# PGTN021_octasource_mkii_controls.net
KiCad netlist of a schematic drawn in EAGLE
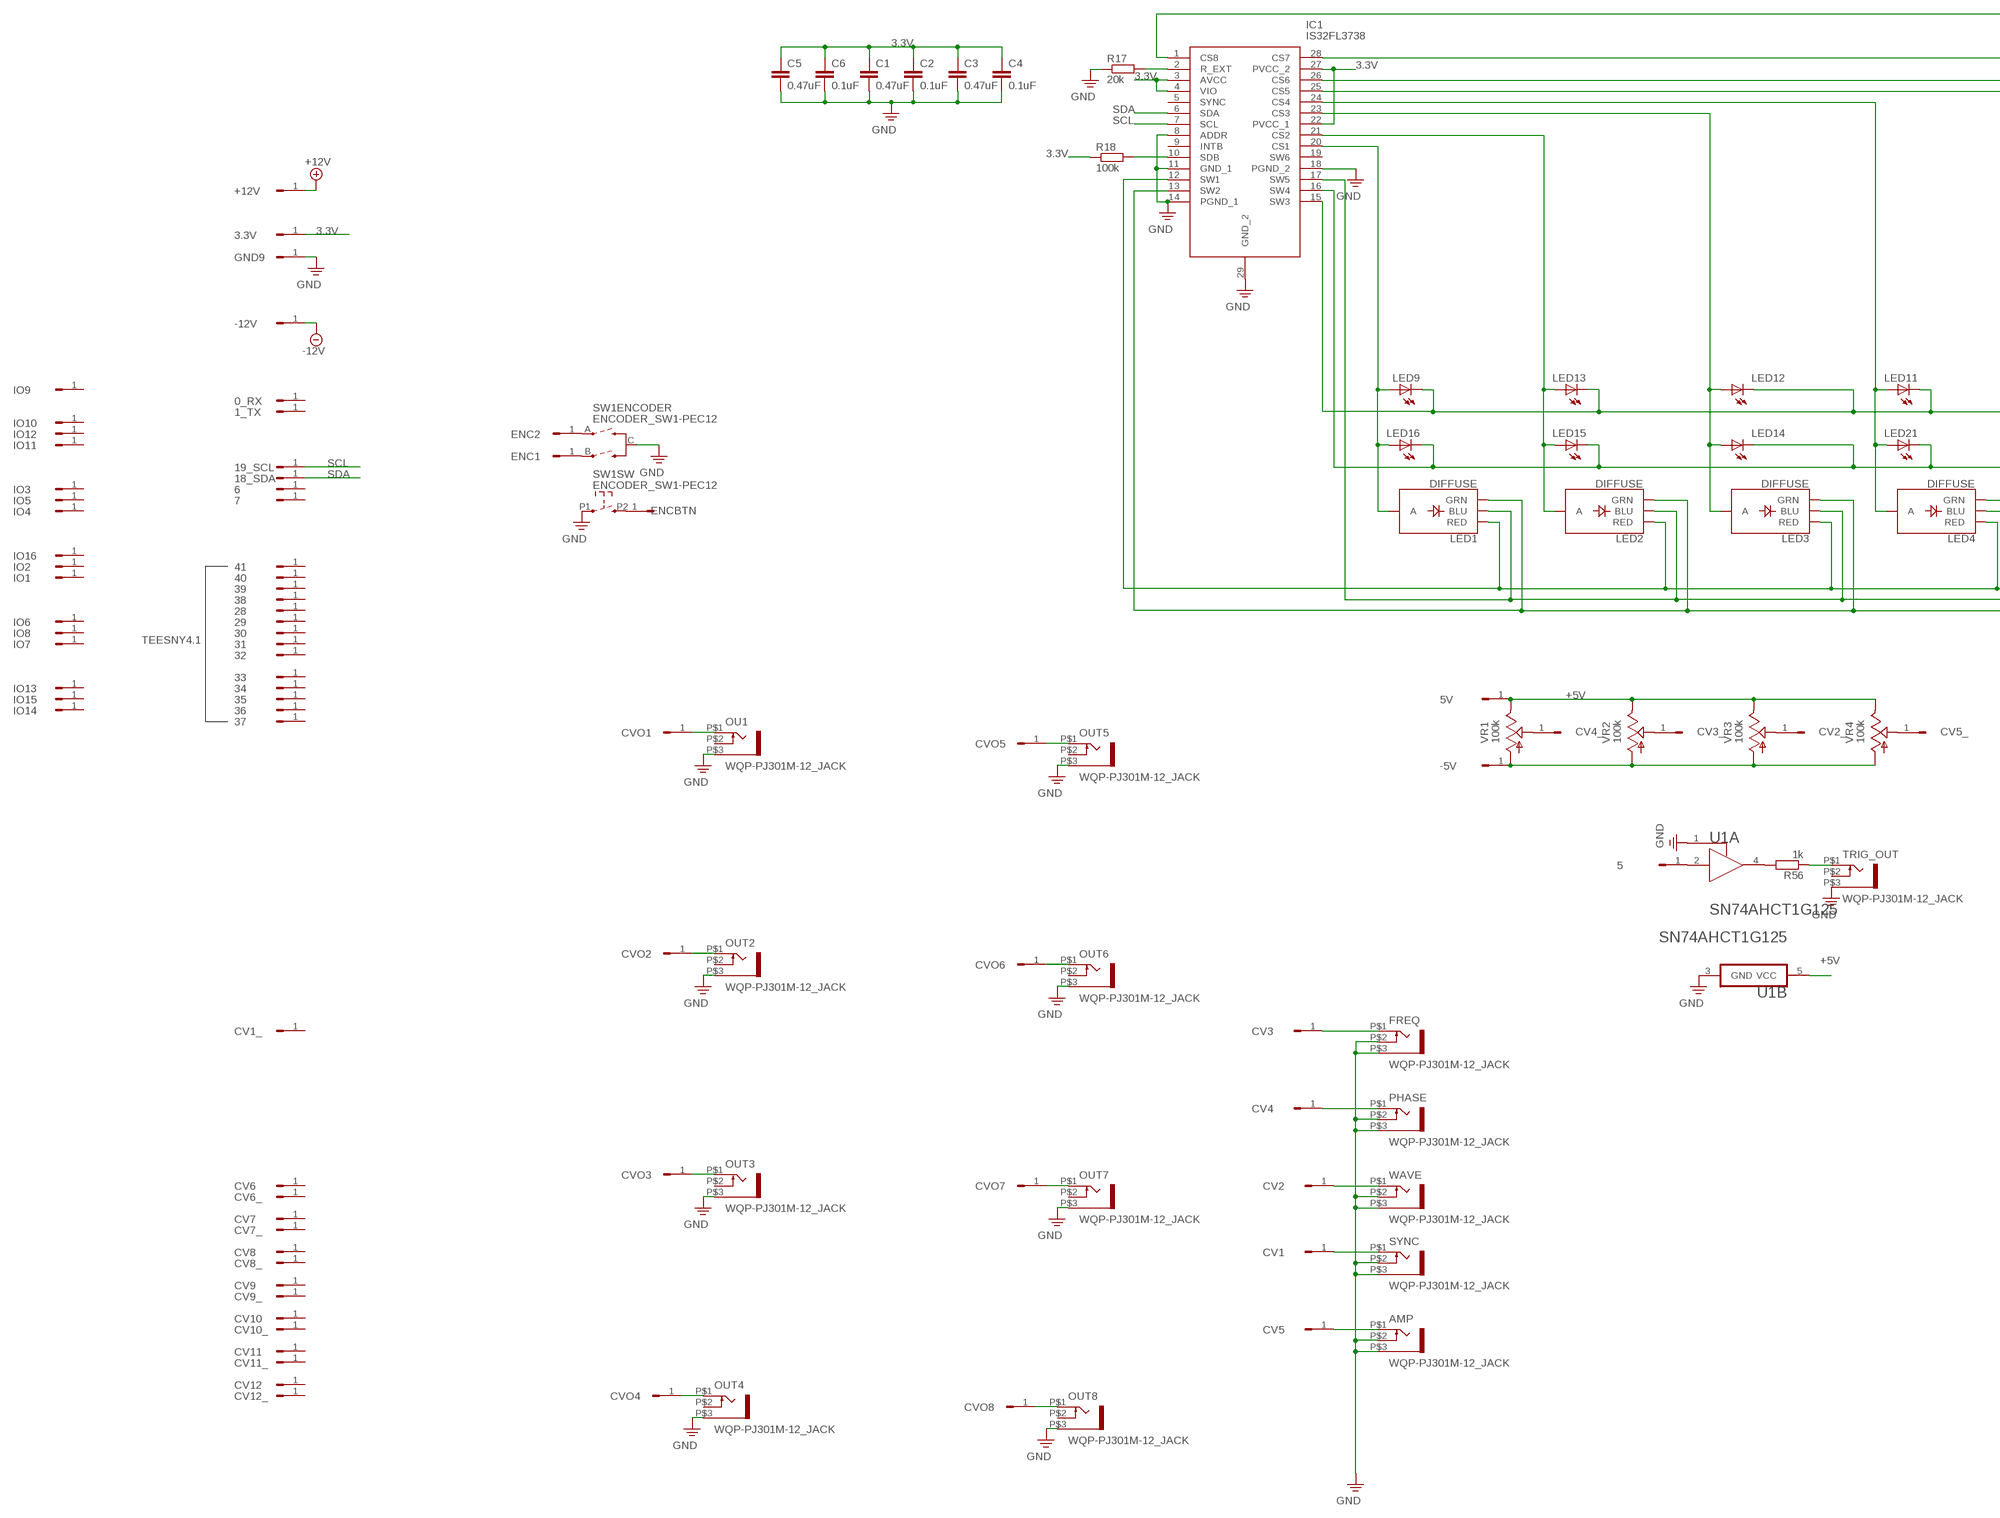
[diagram p0: schematic, sheet 1, part 1 of 2]
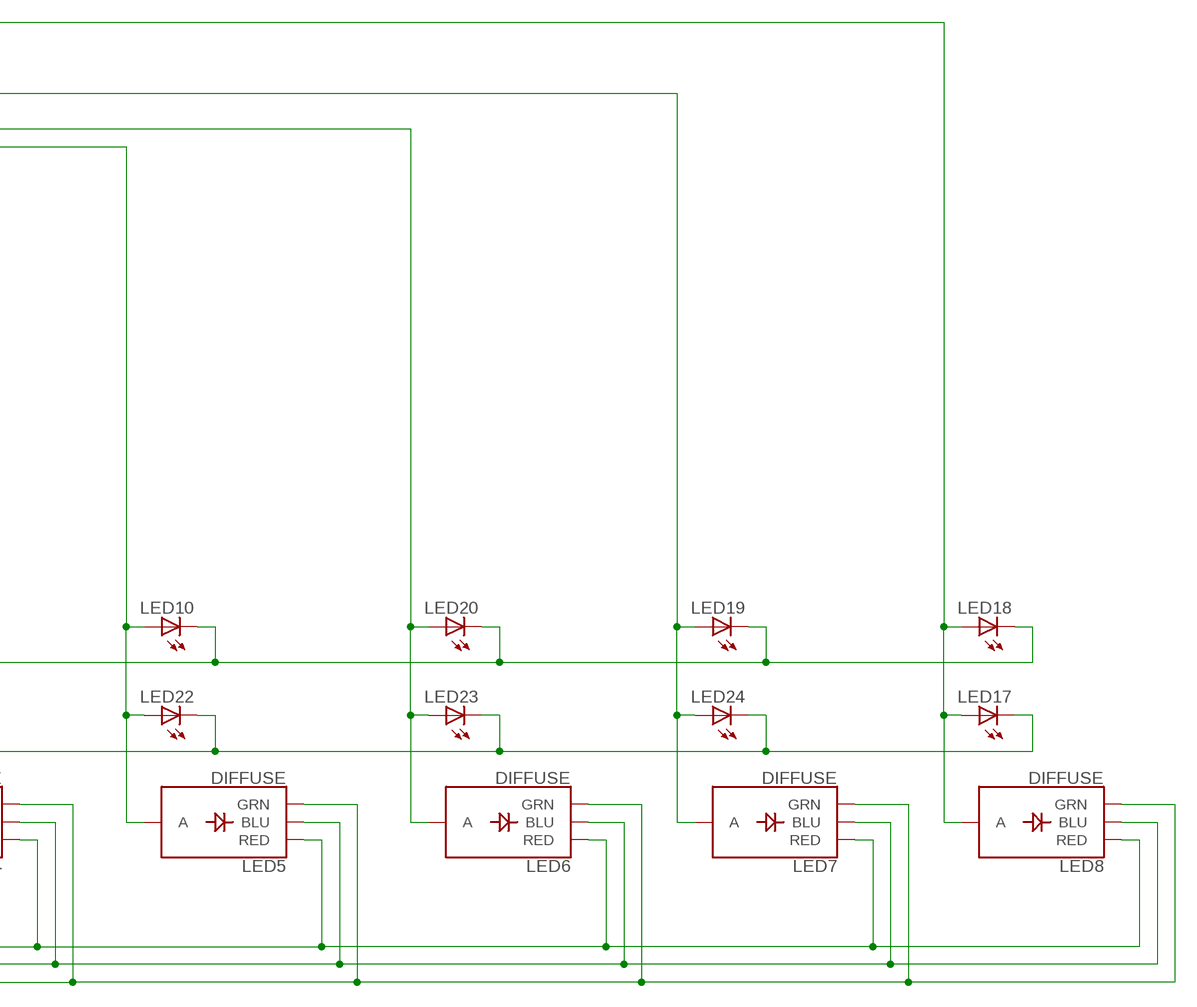
[diagram p1: schematic, sheet 1, part 2 of 2]

(export (version "E")
  (design (tool "Eeschema 10.0.6"))
  (components
    (comp (ref "+12V")
      (value "HEADER/MALE/01")
      (footprint "eagle-import:HEADER_MALE_01")
      (fields (field (name "SPICEPREFIX") "X"))
      (libsource (lib "eagle-import") (part "HEADER/MALE/01"))
    )
    (comp (ref "-5V")
      (value "HEADER/MALE/01")
      (footprint "eagle-import:HEADER_MALE_01")
      (fields (field (name "SPICEPREFIX") "X"))
      (libsource (lib "eagle-import") (part "HEADER/MALE/01"))
    )
    (comp (ref "-12V")
      (value "HEADER/MALE/01")
      (footprint "eagle-import:HEADER_MALE_01")
      (fields (field (name "SPICEPREFIX") "X"))
      (libsource (lib "eagle-import") (part "HEADER/MALE/01"))
    )
    (comp (ref "0_RX")
      (value "HEADER/MALE/01")
      (footprint "eagle-import:HEADER_MALE_01")
      (fields (field (name "SPICEPREFIX") "X"))
      (libsource (lib "eagle-import") (part "HEADER/MALE/01"))
    )
    (comp (ref "1_TX")
      (value "HEADER/MALE/01")
      (footprint "eagle-import:HEADER_MALE_01")
      (fields (field (name "SPICEPREFIX") "X"))
      (libsource (lib "eagle-import") (part "HEADER/MALE/01"))
    )
    (comp (ref "3.3V")
      (value "HEADER/MALE/01")
      (footprint "eagle-import:HEADER_MALE_01")
      (fields (field (name "SPICEPREFIX") "X"))
      (libsource (lib "eagle-import") (part "HEADER/MALE/01"))
    )
    (comp (ref "5")
      (value "HEADER/MALE/01")
      (footprint "eagle-import:HEADER_MALE_01")
      (fields (field (name "SPICEPREFIX") "X"))
      (libsource (lib "eagle-import") (part "HEADER/MALE/01"))
    )
    (comp (ref "5V")
      (value "HEADER/MALE/01")
      (footprint "eagle-import:HEADER_MALE_01")
      (fields (field (name "SPICEPREFIX") "X"))
      (libsource (lib "eagle-import") (part "HEADER/MALE/01"))
    )
    (comp (ref "6")
      (value "HEADER/MALE/01")
      (footprint "eagle-import:HEADER_MALE_01")
      (fields (field (name "SPICEPREFIX") "X"))
      (libsource (lib "eagle-import") (part "HEADER/MALE/01"))
    )
    (comp (ref "7")
      (value "HEADER/MALE/01")
      (footprint "eagle-import:HEADER_MALE_01")
      (fields (field (name "SPICEPREFIX") "X"))
      (libsource (lib "eagle-import") (part "HEADER/MALE/01"))
    )
    (comp (ref "18_SDA")
      (value "HEADER/MALE/01")
      (footprint "eagle-import:HEADER_MALE_01")
      (fields (field (name "SPICEPREFIX") "X"))
      (libsource (lib "eagle-import") (part "HEADER/MALE/01"))
    )
    (comp (ref "19_SCL")
      (value "HEADER/MALE/01")
      (footprint "eagle-import:HEADER_MALE_01")
      (fields (field (name "SPICEPREFIX") "X"))
      (libsource (lib "eagle-import") (part "HEADER/MALE/01"))
    )
    (comp (ref "28")
      (value "HEADER/MALE/01")
      (footprint "eagle-import:HEADER_MALE_01")
      (fields (field (name "SPICEPREFIX") "X"))
      (libsource (lib "eagle-import") (part "HEADER/MALE/01"))
    )
    (comp (ref "29")
      (value "HEADER/MALE/01")
      (footprint "eagle-import:HEADER_MALE_01")
      (fields (field (name "SPICEPREFIX") "X"))
      (libsource (lib "eagle-import") (part "HEADER/MALE/01"))
    )
    (comp (ref "30")
      (value "HEADER/MALE/01")
      (footprint "eagle-import:HEADER_MALE_01")
      (fields (field (name "SPICEPREFIX") "X"))
      (libsource (lib "eagle-import") (part "HEADER/MALE/01"))
    )
    (comp (ref "31")
      (value "HEADER/MALE/01")
      (footprint "eagle-import:HEADER_MALE_01")
      (fields (field (name "SPICEPREFIX") "X"))
      (libsource (lib "eagle-import") (part "HEADER/MALE/01"))
    )
    (comp (ref "32")
      (value "HEADER/MALE/01")
      (footprint "eagle-import:HEADER_MALE_01")
      (fields (field (name "SPICEPREFIX") "X"))
      (libsource (lib "eagle-import") (part "HEADER/MALE/01"))
    )
    (comp (ref "33")
      (value "HEADER/MALE/01")
      (footprint "eagle-import:HEADER_MALE_01")
      (fields (field (name "SPICEPREFIX") "X"))
      (libsource (lib "eagle-import") (part "HEADER/MALE/01"))
    )
    (comp (ref "34")
      (value "HEADER/MALE/01")
      (footprint "eagle-import:HEADER_MALE_01")
      (fields (field (name "SPICEPREFIX") "X"))
      (libsource (lib "eagle-import") (part "HEADER/MALE/01"))
    )
    (comp (ref "35")
      (value "HEADER/MALE/01")
      (footprint "eagle-import:HEADER_MALE_01")
      (fields (field (name "SPICEPREFIX") "X"))
      (libsource (lib "eagle-import") (part "HEADER/MALE/01"))
    )
    (comp (ref "36")
      (value "HEADER/MALE/01")
      (footprint "eagle-import:HEADER_MALE_01")
      (fields (field (name "SPICEPREFIX") "X"))
      (libsource (lib "eagle-import") (part "HEADER/MALE/01"))
    )
    (comp (ref "37")
      (value "HEADER/MALE/01")
      (footprint "eagle-import:HEADER_MALE_01")
      (fields (field (name "SPICEPREFIX") "X"))
      (libsource (lib "eagle-import") (part "HEADER/MALE/01"))
    )
    (comp (ref "38")
      (value "HEADER/MALE/01")
      (footprint "eagle-import:HEADER_MALE_01")
      (fields (field (name "SPICEPREFIX") "X"))
      (libsource (lib "eagle-import") (part "HEADER/MALE/01"))
    )
    (comp (ref "39")
      (value "HEADER/MALE/01")
      (footprint "eagle-import:HEADER_MALE_01")
      (fields (field (name "SPICEPREFIX") "X"))
      (libsource (lib "eagle-import") (part "HEADER/MALE/01"))
    )
    (comp (ref "40")
      (value "HEADER/MALE/01")
      (footprint "eagle-import:HEADER_MALE_01")
      (fields (field (name "SPICEPREFIX") "X"))
      (libsource (lib "eagle-import") (part "HEADER/MALE/01"))
    )
    (comp (ref "41")
      (value "HEADER/MALE/01")
      (footprint "eagle-import:HEADER_MALE_01")
      (fields (field (name "SPICEPREFIX") "X"))
      (libsource (lib "eagle-import") (part "HEADER/MALE/01"))
    )
    (comp (ref "AMP")
      (value "WQP-PJ301M-12_JACK")
      (footprint "eagle-import:WQP-PJ301M-12_JACK")
      (libsource (lib "eagle-import") (part "WQP-PJ301M-12_JACK"))
    )
    (comp (ref "C1")
      (value "0.47uF")
      (footprint "eagle-import:C0603")
      (libsource (lib "eagle-import") (part "CAPACITORC0603"))
    )
    (comp (ref "C2")
      (value "0.1uF")
      (footprint "eagle-import:C0603")
      (libsource (lib "eagle-import") (part "CAPACITORC0603"))
    )
    (comp (ref "C3")
      (value "0.47uF")
      (footprint "eagle-import:C0603")
      (libsource (lib "eagle-import") (part "CAPACITORC0603"))
    )
    (comp (ref "C4")
      (value "0.1uF")
      (footprint "eagle-import:C0603")
      (libsource (lib "eagle-import") (part "CAPACITORC0603"))
    )
    (comp (ref "C5")
      (value "0.47uF")
      (footprint "eagle-import:C0603")
      (libsource (lib "eagle-import") (part "CAPACITORC0603"))
    )
    (comp (ref "C6")
      (value "0.1uF")
      (footprint "eagle-import:C0603")
      (libsource (lib "eagle-import") (part "CAPACITORC0603"))
    )
    (comp (ref "CV1")
      (value "HEADER/MALE/01")
      (footprint "eagle-import:HEADER_MALE_01")
      (fields (field (name "SPICEPREFIX") "X"))
      (libsource (lib "eagle-import") (part "HEADER/MALE/01"))
    )
    (comp (ref "CV1_")
      (value "HEADER/MALE/01")
      (footprint "eagle-import:HEADER_MALE_01")
      (fields (field (name "SPICEPREFIX") "X"))
      (libsource (lib "eagle-import") (part "HEADER/MALE/01"))
    )
    (comp (ref "CV2")
      (value "HEADER/MALE/01")
      (footprint "eagle-import:HEADER_MALE_01")
      (fields (field (name "SPICEPREFIX") "X"))
      (libsource (lib "eagle-import") (part "HEADER/MALE/01"))
    )
    (comp (ref "CV2_")
      (value "HEADER/MALE/01")
      (footprint "eagle-import:HEADER_MALE_01")
      (fields (field (name "SPICEPREFIX") "X"))
      (libsource (lib "eagle-import") (part "HEADER/MALE/01"))
    )
    (comp (ref "CV3")
      (value "HEADER/MALE/01")
      (footprint "eagle-import:HEADER_MALE_01")
      (fields (field (name "SPICEPREFIX") "X"))
      (libsource (lib "eagle-import") (part "HEADER/MALE/01"))
    )
    (comp (ref "CV3_")
      (value "HEADER/MALE/01")
      (footprint "eagle-import:HEADER_MALE_01")
      (fields (field (name "SPICEPREFIX") "X"))
      (libsource (lib "eagle-import") (part "HEADER/MALE/01"))
    )
    (comp (ref "CV4")
      (value "HEADER/MALE/01")
      (footprint "eagle-import:HEADER_MALE_01")
      (fields (field (name "SPICEPREFIX") "X"))
      (libsource (lib "eagle-import") (part "HEADER/MALE/01"))
    )
    (comp (ref "CV4_")
      (value "HEADER/MALE/01")
      (footprint "eagle-import:HEADER_MALE_01")
      (fields (field (name "SPICEPREFIX") "X"))
      (libsource (lib "eagle-import") (part "HEADER/MALE/01"))
    )
    (comp (ref "CV5")
      (value "HEADER/MALE/01")
      (footprint "eagle-import:HEADER_MALE_01")
      (fields (field (name "SPICEPREFIX") "X"))
      (libsource (lib "eagle-import") (part "HEADER/MALE/01"))
    )
    (comp (ref "CV5_")
      (value "HEADER/MALE/01")
      (footprint "eagle-import:HEADER_MALE_01")
      (fields (field (name "SPICEPREFIX") "X"))
      (libsource (lib "eagle-import") (part "HEADER/MALE/01"))
    )
    (comp (ref "CV6")
      (value "HEADER/MALE/01")
      (footprint "eagle-import:HEADER_MALE_01")
      (fields (field (name "SPICEPREFIX") "X"))
      (libsource (lib "eagle-import") (part "HEADER/MALE/01"))
    )
    (comp (ref "CV6_")
      (value "HEADER/MALE/01")
      (footprint "eagle-import:HEADER_MALE_01")
      (fields (field (name "SPICEPREFIX") "X"))
      (libsource (lib "eagle-import") (part "HEADER/MALE/01"))
    )
    (comp (ref "CV7")
      (value "HEADER/MALE/01")
      (footprint "eagle-import:HEADER_MALE_01")
      (fields (field (name "SPICEPREFIX") "X"))
      (libsource (lib "eagle-import") (part "HEADER/MALE/01"))
    )
    (comp (ref "CV7_")
      (value "HEADER/MALE/01")
      (footprint "eagle-import:HEADER_MALE_01")
      (fields (field (name "SPICEPREFIX") "X"))
      (libsource (lib "eagle-import") (part "HEADER/MALE/01"))
    )
    (comp (ref "CV8")
      (value "HEADER/MALE/01")
      (footprint "eagle-import:HEADER_MALE_01")
      (fields (field (name "SPICEPREFIX") "X"))
      (libsource (lib "eagle-import") (part "HEADER/MALE/01"))
    )
    (comp (ref "CV8_")
      (value "HEADER/MALE/01")
      (footprint "eagle-import:HEADER_MALE_01")
      (fields (field (name "SPICEPREFIX") "X"))
      (libsource (lib "eagle-import") (part "HEADER/MALE/01"))
    )
    (comp (ref "CV9")
      (value "HEADER/MALE/01")
      (footprint "eagle-import:HEADER_MALE_01")
      (fields (field (name "SPICEPREFIX") "X"))
      (libsource (lib "eagle-import") (part "HEADER/MALE/01"))
    )
    (comp (ref "CV9_")
      (value "HEADER/MALE/01")
      (footprint "eagle-import:HEADER_MALE_01")
      (fields (field (name "SPICEPREFIX") "X"))
      (libsource (lib "eagle-import") (part "HEADER/MALE/01"))
    )
    (comp (ref "CV10")
      (value "HEADER/MALE/01")
      (footprint "eagle-import:HEADER_MALE_01")
      (fields (field (name "SPICEPREFIX") "X"))
      (libsource (lib "eagle-import") (part "HEADER/MALE/01"))
    )
    (comp (ref "CV10_")
      (value "HEADER/MALE/01")
      (footprint "eagle-import:HEADER_MALE_01")
      (fields (field (name "SPICEPREFIX") "X"))
      (libsource (lib "eagle-import") (part "HEADER/MALE/01"))
    )
    (comp (ref "CV11")
      (value "HEADER/MALE/01")
      (footprint "eagle-import:HEADER_MALE_01")
      (fields (field (name "SPICEPREFIX") "X"))
      (libsource (lib "eagle-import") (part "HEADER/MALE/01"))
    )
    (comp (ref "CV11_")
      (value "HEADER/MALE/01")
      (footprint "eagle-import:HEADER_MALE_01")
      (fields (field (name "SPICEPREFIX") "X"))
      (libsource (lib "eagle-import") (part "HEADER/MALE/01"))
    )
    (comp (ref "CV12")
      (value "HEADER/MALE/01")
      (footprint "eagle-import:HEADER_MALE_01")
      (fields (field (name "SPICEPREFIX") "X"))
      (libsource (lib "eagle-import") (part "HEADER/MALE/01"))
    )
    (comp (ref "CV12_")
      (value "HEADER/MALE/01")
      (footprint "eagle-import:HEADER_MALE_01")
      (fields (field (name "SPICEPREFIX") "X"))
      (libsource (lib "eagle-import") (part "HEADER/MALE/01"))
    )
    (comp (ref "CVO1")
      (value "HEADER/MALE/01")
      (footprint "eagle-import:HEADER_MALE_01")
      (fields (field (name "SPICEPREFIX") "X"))
      (libsource (lib "eagle-import") (part "HEADER/MALE/01"))
    )
    (comp (ref "CVO2")
      (value "HEADER/MALE/01")
      (footprint "eagle-import:HEADER_MALE_01")
      (fields (field (name "SPICEPREFIX") "X"))
      (libsource (lib "eagle-import") (part "HEADER/MALE/01"))
    )
    (comp (ref "CVO3")
      (value "HEADER/MALE/01")
      (footprint "eagle-import:HEADER_MALE_01")
      (fields (field (name "SPICEPREFIX") "X"))
      (libsource (lib "eagle-import") (part "HEADER/MALE/01"))
    )
    (comp (ref "CVO4")
      (value "HEADER/MALE/01")
      (footprint "eagle-import:HEADER_MALE_01")
      (fields (field (name "SPICEPREFIX") "X"))
      (libsource (lib "eagle-import") (part "HEADER/MALE/01"))
    )
    (comp (ref "CVO5")
      (value "HEADER/MALE/01")
      (footprint "eagle-import:HEADER_MALE_01")
      (fields (field (name "SPICEPREFIX") "X"))
      (libsource (lib "eagle-import") (part "HEADER/MALE/01"))
    )
    (comp (ref "CVO6")
      (value "HEADER/MALE/01")
      (footprint "eagle-import:HEADER_MALE_01")
      (fields (field (name "SPICEPREFIX") "X"))
      (libsource (lib "eagle-import") (part "HEADER/MALE/01"))
    )
    (comp (ref "CVO7")
      (value "HEADER/MALE/01")
      (footprint "eagle-import:HEADER_MALE_01")
      (fields (field (name "SPICEPREFIX") "X"))
      (libsource (lib "eagle-import") (part "HEADER/MALE/01"))
    )
    (comp (ref "CVO8")
      (value "HEADER/MALE/01")
      (footprint "eagle-import:HEADER_MALE_01")
      (fields (field (name "SPICEPREFIX") "X"))
      (libsource (lib "eagle-import") (part "HEADER/MALE/01"))
    )
    (comp (ref "ENC1")
      (value "HEADER/MALE/01")
      (footprint "eagle-import:HEADER_MALE_01")
      (fields (field (name "SPICEPREFIX") "X"))
      (libsource (lib "eagle-import") (part "HEADER/MALE/01"))
    )
    (comp (ref "ENC2")
      (value "HEADER/MALE/01")
      (footprint "eagle-import:HEADER_MALE_01")
      (fields (field (name "SPICEPREFIX") "X"))
      (libsource (lib "eagle-import") (part "HEADER/MALE/01"))
    )
    (comp (ref "ENCBTN")
      (value "HEADER/MALE/01")
      (footprint "eagle-import:HEADER_MALE_01")
      (fields (field (name "SPICEPREFIX") "X"))
      (libsource (lib "eagle-import") (part "HEADER/MALE/01"))
    )
    (comp (ref "FREQ")
      (value "WQP-PJ301M-12_JACK")
      (footprint "eagle-import:WQP-PJ301M-12_JACK")
      (libsource (lib "eagle-import") (part "WQP-PJ301M-12_JACK"))
    )
    (comp (ref "GND9")
      (value "HEADER/MALE/01")
      (footprint "eagle-import:HEADER_MALE_01")
      (fields (field (name "SPICEPREFIX") "X"))
      (libsource (lib "eagle-import") (part "HEADER/MALE/01"))
    )
    (comp (ref "IC1")
      (value "IS32FL3738")
      (footprint "eagle-import:TSSOP29")
      (fields (field (name "MANUFACTURER_PART_NUMBER") "IS32FL3738-ZLA3-TR"))
      (libsource (lib "eagle-import") (part "IS32FL3738"))
    )
    (comp (ref "IO1")
      (value "HEADER/MALE/01")
      (footprint "eagle-import:HEADER_MALE_01")
      (fields (field (name "SPICEPREFIX") "X"))
      (libsource (lib "eagle-import") (part "HEADER/MALE/01"))
    )
    (comp (ref "IO2")
      (value "HEADER/MALE/01")
      (footprint "eagle-import:HEADER_MALE_01")
      (fields (field (name "SPICEPREFIX") "X"))
      (libsource (lib "eagle-import") (part "HEADER/MALE/01"))
    )
    (comp (ref "IO3")
      (value "HEADER/MALE/01")
      (footprint "eagle-import:HEADER_MALE_01")
      (fields (field (name "SPICEPREFIX") "X"))
      (libsource (lib "eagle-import") (part "HEADER/MALE/01"))
    )
    (comp (ref "IO4")
      (value "HEADER/MALE/01")
      (footprint "eagle-import:HEADER_MALE_01")
      (fields (field (name "SPICEPREFIX") "X"))
      (libsource (lib "eagle-import") (part "HEADER/MALE/01"))
    )
    (comp (ref "IO5")
      (value "HEADER/MALE/01")
      (footprint "eagle-import:HEADER_MALE_01")
      (fields (field (name "SPICEPREFIX") "X"))
      (libsource (lib "eagle-import") (part "HEADER/MALE/01"))
    )
    (comp (ref "IO6")
      (value "HEADER/MALE/01")
      (footprint "eagle-import:HEADER_MALE_01")
      (fields (field (name "SPICEPREFIX") "X"))
      (libsource (lib "eagle-import") (part "HEADER/MALE/01"))
    )
    (comp (ref "IO7")
      (value "HEADER/MALE/01")
      (footprint "eagle-import:HEADER_MALE_01")
      (fields (field (name "SPICEPREFIX") "X"))
      (libsource (lib "eagle-import") (part "HEADER/MALE/01"))
    )
    (comp (ref "IO8")
      (value "HEADER/MALE/01")
      (footprint "eagle-import:HEADER_MALE_01")
      (fields (field (name "SPICEPREFIX") "X"))
      (libsource (lib "eagle-import") (part "HEADER/MALE/01"))
    )
    (comp (ref "IO9")
      (value "HEADER/MALE/01")
      (footprint "eagle-import:HEADER_MALE_01")
      (fields (field (name "SPICEPREFIX") "X"))
      (libsource (lib "eagle-import") (part "HEADER/MALE/01"))
    )
    (comp (ref "IO10")
      (value "HEADER/MALE/01")
      (footprint "eagle-import:HEADER_MALE_01")
      (fields (field (name "SPICEPREFIX") "X"))
      (libsource (lib "eagle-import") (part "HEADER/MALE/01"))
    )
    (comp (ref "IO11")
      (value "HEADER/MALE/01")
      (footprint "eagle-import:HEADER_MALE_01")
      (fields (field (name "SPICEPREFIX") "X"))
      (libsource (lib "eagle-import") (part "HEADER/MALE/01"))
    )
    (comp (ref "IO12")
      (value "HEADER/MALE/01")
      (footprint "eagle-import:HEADER_MALE_01")
      (fields (field (name "SPICEPREFIX") "X"))
      (libsource (lib "eagle-import") (part "HEADER/MALE/01"))
    )
    (comp (ref "IO13")
      (value "HEADER/MALE/01")
      (footprint "eagle-import:HEADER_MALE_01")
      (fields (field (name "SPICEPREFIX") "X"))
      (libsource (lib "eagle-import") (part "HEADER/MALE/01"))
    )
    (comp (ref "IO14")
      (value "HEADER/MALE/01")
      (footprint "eagle-import:HEADER_MALE_01")
      (fields (field (name "SPICEPREFIX") "X"))
      (libsource (lib "eagle-import") (part "HEADER/MALE/01"))
    )
    (comp (ref "IO15")
      (value "HEADER/MALE/01")
      (footprint "eagle-import:HEADER_MALE_01")
      (fields (field (name "SPICEPREFIX") "X"))
      (libsource (lib "eagle-import") (part "HEADER/MALE/01"))
    )
    (comp (ref "IO16")
      (value "HEADER/MALE/01")
      (footprint "eagle-import:HEADER_MALE_01")
      (fields (field (name "SPICEPREFIX") "X"))
      (libsource (lib "eagle-import") (part "HEADER/MALE/01"))
    )
    (comp (ref "LED1")
      (value "DIFFUSE")
      (footprint "eagle-import:LED-RGB-THRU")
      (libsource (lib "eagle-import") (part "LED-RGB-CADIFFUSE"))
    )
    (comp (ref "LED2")
      (value "DIFFUSE")
      (footprint "eagle-import:LED-RGB-THRU")
      (libsource (lib "eagle-import") (part "LED-RGB-CADIFFUSE"))
    )
    (comp (ref "LED3")
      (value "DIFFUSE")
      (footprint "eagle-import:LED-RGB-THRU")
      (libsource (lib "eagle-import") (part "LED-RGB-CADIFFUSE"))
    )
    (comp (ref "LED4")
      (value "DIFFUSE")
      (footprint "eagle-import:LED-RGB-THRU")
      (libsource (lib "eagle-import") (part "LED-RGB-CADIFFUSE"))
    )
    (comp (ref "LED5")
      (value "DIFFUSE")
      (footprint "eagle-import:LED-RGB-THRU")
      (libsource (lib "eagle-import") (part "LED-RGB-CADIFFUSE"))
    )
    (comp (ref "LED6")
      (value "DIFFUSE")
      (footprint "eagle-import:LED-RGB-THRU")
      (libsource (lib "eagle-import") (part "LED-RGB-CADIFFUSE"))
    )
    (comp (ref "LED7")
      (value "DIFFUSE")
      (footprint "eagle-import:LED-RGB-THRU")
      (libsource (lib "eagle-import") (part "LED-RGB-CADIFFUSE"))
    )
    (comp (ref "LED8")
      (value "DIFFUSE")
      (footprint "eagle-import:LED-RGB-THRU")
      (libsource (lib "eagle-import") (part "LED-RGB-CADIFFUSE"))
    )
    (comp (ref "LED9")
      (value "LEDCHIPLED_0805")
      (footprint "eagle-import:CHIPLED_0805")
      (libsource (lib "eagle-import") (part "LEDCHIPLED_0805"))
    )
    (comp (ref "LED10")
      (value "LEDCHIPLED_0805")
      (footprint "eagle-import:CHIPLED_0805")
      (libsource (lib "eagle-import") (part "LEDCHIPLED_0805"))
    )
    (comp (ref "LED11")
      (value "LEDCHIPLED_0805")
      (footprint "eagle-import:CHIPLED_0805")
      (libsource (lib "eagle-import") (part "LEDCHIPLED_0805"))
    )
    (comp (ref "LED12")
      (value "LEDCHIPLED_0805")
      (footprint "eagle-import:CHIPLED_0805")
      (libsource (lib "eagle-import") (part "LEDCHIPLED_0805"))
    )
    (comp (ref "LED13")
      (value "LEDCHIPLED_0805")
      (footprint "eagle-import:CHIPLED_0805")
      (libsource (lib "eagle-import") (part "LEDCHIPLED_0805"))
    )
    (comp (ref "LED14")
      (value "LEDCHIPLED_0805")
      (footprint "eagle-import:CHIPLED_0805")
      (libsource (lib "eagle-import") (part "LEDCHIPLED_0805"))
    )
    (comp (ref "LED15")
      (value "LEDCHIPLED_0805")
      (footprint "eagle-import:CHIPLED_0805")
      (libsource (lib "eagle-import") (part "LEDCHIPLED_0805"))
    )
    (comp (ref "LED16")
      (value "LEDCHIPLED_0805")
      (footprint "eagle-import:CHIPLED_0805")
      (libsource (lib "eagle-import") (part "LEDCHIPLED_0805"))
    )
    (comp (ref "LED17")
      (value "LEDCHIPLED_0805")
      (footprint "eagle-import:CHIPLED_0805")
      (libsource (lib "eagle-import") (part "LEDCHIPLED_0805"))
    )
    (comp (ref "LED18")
      (value "LEDCHIPLED_0805")
      (footprint "eagle-import:CHIPLED_0805")
      (libsource (lib "eagle-import") (part "LEDCHIPLED_0805"))
    )
    (comp (ref "LED19")
      (value "LEDCHIPLED_0805")
      (footprint "eagle-import:CHIPLED_0805")
      (libsource (lib "eagle-import") (part "LEDCHIPLED_0805"))
    )
    (comp (ref "LED20")
      (value "LEDCHIPLED_0805")
      (footprint "eagle-import:CHIPLED_0805")
      (libsource (lib "eagle-import") (part "LEDCHIPLED_0805"))
    )
    (comp (ref "LED21")
      (value "LEDCHIPLED_0805")
      (footprint "eagle-import:CHIPLED_0805")
      (libsource (lib "eagle-import") (part "LEDCHIPLED_0805"))
    )
    (comp (ref "LED22")
      (value "LEDCHIPLED_0805")
      (footprint "eagle-import:CHIPLED_0805")
      (libsource (lib "eagle-import") (part "LEDCHIPLED_0805"))
    )
    (comp (ref "LED23")
      (value "LEDCHIPLED_0805")
      (footprint "eagle-import:CHIPLED_0805")
      (libsource (lib "eagle-import") (part "LEDCHIPLED_0805"))
    )
    (comp (ref "LED24")
      (value "LEDCHIPLED_0805")
      (footprint "eagle-import:CHIPLED_0805")
      (libsource (lib "eagle-import") (part "LEDCHIPLED_0805"))
    )
    (comp (ref "OU1")
      (value "WQP-PJ301M-12_JACK")
      (footprint "eagle-import:WQP-PJ301M-12_JACK")
      (libsource (lib "eagle-import") (part "WQP-PJ301M-12_JACK"))
    )
    (comp (ref "OUT2")
      (value "WQP-PJ301M-12_JACK")
      (footprint "eagle-import:WQP-PJ301M-12_JACK")
      (libsource (lib "eagle-import") (part "WQP-PJ301M-12_JACK"))
    )
    (comp (ref "OUT3")
      (value "WQP-PJ301M-12_JACK")
      (footprint "eagle-import:WQP-PJ301M-12_JACK")
      (libsource (lib "eagle-import") (part "WQP-PJ301M-12_JACK"))
    )
    (comp (ref "OUT4")
      (value "WQP-PJ301M-12_JACK")
      (footprint "eagle-import:WQP-PJ301M-12_JACK")
      (libsource (lib "eagle-import") (part "WQP-PJ301M-12_JACK"))
    )
    (comp (ref "OUT5")
      (value "WQP-PJ301M-12_JACK")
      (footprint "eagle-import:WQP-PJ301M-12_JACK")
      (libsource (lib "eagle-import") (part "WQP-PJ301M-12_JACK"))
    )
    (comp (ref "OUT6")
      (value "WQP-PJ301M-12_JACK")
      (footprint "eagle-import:WQP-PJ301M-12_JACK")
      (libsource (lib "eagle-import") (part "WQP-PJ301M-12_JACK"))
    )
    (comp (ref "OUT7")
      (value "WQP-PJ301M-12_JACK")
      (footprint "eagle-import:WQP-PJ301M-12_JACK")
      (libsource (lib "eagle-import") (part "WQP-PJ301M-12_JACK"))
    )
    (comp (ref "OUT8")
      (value "WQP-PJ301M-12_JACK")
      (footprint "eagle-import:WQP-PJ301M-12_JACK")
      (libsource (lib "eagle-import") (part "WQP-PJ301M-12_JACK"))
    )
    (comp (ref "PHASE")
      (value "WQP-PJ301M-12_JACK")
      (footprint "eagle-import:WQP-PJ301M-12_JACK")
      (libsource (lib "eagle-import") (part "WQP-PJ301M-12_JACK"))
    )
    (comp (ref "R17")
      (value "20k")
      (footprint "eagle-import:R0603")
      (libsource (lib "eagle-import") (part "RESISTOR"))
    )
    (comp (ref "R18")
      (value "100k")
      (footprint "eagle-import:R0603")
      (libsource (lib "eagle-import") (part "RESISTOR"))
    )
    (comp (ref "R56")
      (value "1k")
      (footprint "eagle-import:R0603")
      (libsource (lib "eagle-import") (part "RESISTOR"))
    )
    (comp (ref "SW1")
      (value "ENCODER_SW1-PEC12")
      (footprint "eagle-import:PEC12_INCREMENTAL_ENCODER")
      (libsource (lib "eagle-import") (part "ENCODER_SW1-PEC12"))
    )
    (comp (ref "SYNC")
      (value "WQP-PJ301M-12_JACK")
      (footprint "eagle-import:WQP-PJ301M-12_JACK")
      (libsource (lib "eagle-import") (part "WQP-PJ301M-12_JACK"))
    )
    (comp (ref "TRIG_OUT")
      (value "WQP-PJ301M-12_JACK")
      (footprint "eagle-import:WQP-PJ301M-12_JACK")
      (libsource (lib "eagle-import") (part "WQP-PJ301M-12_JACK"))
    )
    (comp (ref "U1")
      (value "74AHCT1G125\"")
      (footprint "eagle-import:74AHCT1G125")
      (fields (field (name "MF") "Texas Instruments") (field (name "MPN") "SN74AHCT1G125"))
      (libsource (lib "eagle-import") (part "74AHCT1G125{dblquote}"))
    )
    (comp (ref "VR1")
      (value "100k")
      (footprint "eagle-import:9MM_SNAP-IN_POT")
      (libsource (lib "eagle-import") (part "9MM_SNAP-IN_POT_"))
    )
    (comp (ref "VR2")
      (value "100k")
      (footprint "eagle-import:9MM_SNAP-IN_POT")
      (libsource (lib "eagle-import") (part "9MM_SNAP-IN_POT_"))
    )
    (comp (ref "VR3")
      (value "100k")
      (footprint "eagle-import:9MM_SNAP-IN_POT")
      (libsource (lib "eagle-import") (part "9MM_SNAP-IN_POT_"))
    )
    (comp (ref "VR4")
      (value "100k")
      (footprint "eagle-import:9MM_SNAP-IN_POT")
      (libsource (lib "eagle-import") (part "9MM_SNAP-IN_POT_"))
    )
    (comp (ref "WAVE")
      (value "WQP-PJ301M-12_JACK")
      (footprint "eagle-import:WQP-PJ301M-12_JACK")
      (libsource (lib "eagle-import") (part "WQP-PJ301M-12_JACK"))
    )
  )
  (nets
    (net (code "1") (name "+12V") (class "Default")
      (node (ref "+12V") (pin "1") (pinfunction "3_1") (pintype "passive"))
    )
    (net (code "2") (name "-12V") (class "Default")
      (node (ref "-12V") (pin "1") (pinfunction "3_1") (pintype "passive"))
    )
    (net (code "3") (name "/+5V") (class "Default")
      (node (ref "5V") (pin "1") (pinfunction "3_1") (pintype "passive"))
      (node (ref "U1") (pin "5") (pinfunction "VCC_5") (pintype "power_in"))
      (node (ref "VR1") (pin "3") (pinfunction "E_3") (pintype "passive"))
      (node (ref "VR2") (pin "3") (pinfunction "E_3") (pintype "passive"))
      (node (ref "VR3") (pin "3") (pinfunction "E_3") (pintype "passive"))
      (node (ref "VR4") (pin "3") (pinfunction "E_3") (pintype "passive"))
    )
    (net (code "4") (name "/3.3V") (class "Default")
      (node (ref "3.3V") (pin "1") (pinfunction "3_1") (pintype "passive"))
      (node (ref "C1") (pin "1") (pinfunction "1_1") (pintype "passive"))
      (node (ref "C2") (pin "1") (pinfunction "1_1") (pintype "passive"))
      (node (ref "C3") (pin "1") (pinfunction "1_1") (pintype "passive"))
      (node (ref "C4") (pin "1") (pinfunction "1_1") (pintype "passive"))
      (node (ref "C5") (pin "1") (pinfunction "1_1") (pintype "passive"))
      (node (ref "C6") (pin "1") (pinfunction "1_1") (pintype "passive"))
      (node (ref "IC1") (pin "22") (pinfunction "PVCC_1_22") (pintype "power_in"))
      (node (ref "IC1") (pin "27") (pinfunction "PVCC_2_27") (pintype "power_in"))
      (node (ref "IC1") (pin "3") (pinfunction "AVCC_3") (pintype "power_in"))
      (node (ref "IC1") (pin "4") (pinfunction "VIO_4") (pintype "input"))
      (node (ref "R18") (pin "1") (pinfunction "1_1") (pintype "passive"))
    )
    (net (code "5") (name "/SCL") (class "Default")
      (node (ref "19_SCL") (pin "1") (pinfunction "3_1") (pintype "passive"))
      (node (ref "IC1") (pin "7") (pinfunction "SCL_7") (pintype "bidirectional"))
    )
    (net (code "6") (name "/SDA") (class "Default")
      (node (ref "18_SDA") (pin "1") (pinfunction "3_1") (pintype "passive"))
      (node (ref "IC1") (pin "6") (pinfunction "SDA_6") (pintype "bidirectional"))
    )
    (net (code "7") (name "GND") (class "Default")
      (node (ref "AMP") (pin "P$2") (pinfunction "3_P$2") (pintype "passive"))
      (node (ref "AMP") (pin "P$3") (pinfunction "1_P$3") (pintype "passive"))
      (node (ref "C1") (pin "2") (pinfunction "2_2") (pintype "passive"))
      (node (ref "C2") (pin "2") (pinfunction "2_2") (pintype "passive"))
      (node (ref "C3") (pin "2") (pinfunction "2_2") (pintype "passive"))
      (node (ref "C4") (pin "2") (pinfunction "2_2") (pintype "passive"))
      (node (ref "C5") (pin "2") (pinfunction "2_2") (pintype "passive"))
      (node (ref "C6") (pin "2") (pinfunction "2_2") (pintype "passive"))
      (node (ref "FREQ") (pin "P$2") (pinfunction "3_P$2") (pintype "passive"))
      (node (ref "FREQ") (pin "P$3") (pinfunction "1_P$3") (pintype "passive"))
      (node (ref "GND9") (pin "1") (pinfunction "3_1") (pintype "passive"))
      (node (ref "IC1") (pin "11") (pinfunction "GND_1_11") (pintype "power_in"))
      (node (ref "IC1") (pin "14") (pinfunction "PGND_1_14") (pintype "power_in"))
      (node (ref "IC1") (pin "18") (pinfunction "PGND_2_18") (pintype "power_in"))
      (node (ref "IC1") (pin "29") (pinfunction "GND_2_29") (pintype "power_in"))
      (node (ref "IC1") (pin "8") (pinfunction "ADDR_8") (pintype "input"))
      (node (ref "OU1") (pin "P$3") (pinfunction "1_P$3") (pintype "passive"))
      (node (ref "OUT2") (pin "P$3") (pinfunction "1_P$3") (pintype "passive"))
      (node (ref "OUT3") (pin "P$3") (pinfunction "1_P$3") (pintype "passive"))
      (node (ref "OUT4") (pin "P$3") (pinfunction "1_P$3") (pintype "passive"))
      (node (ref "OUT5") (pin "P$3") (pinfunction "1_P$3") (pintype "passive"))
      (node (ref "OUT6") (pin "P$3") (pinfunction "1_P$3") (pintype "passive"))
      (node (ref "OUT7") (pin "P$3") (pinfunction "1_P$3") (pintype "passive"))
      (node (ref "OUT8") (pin "P$3") (pinfunction "1_P$3") (pintype "passive"))
      (node (ref "PHASE") (pin "P$2") (pinfunction "3_P$2") (pintype "passive"))
      (node (ref "PHASE") (pin "P$3") (pinfunction "1_P$3") (pintype "passive"))
      (node (ref "R17") (pin "1") (pinfunction "1_1") (pintype "passive"))
      (node (ref "SW1") (pin "C") (pinfunction "C_C") (pintype "passive"))
      (node (ref "SW1") (pin "P1") (pinfunction "1_P1") (pintype "passive"))
      (node (ref "SYNC") (pin "P$2") (pinfunction "3_P$2") (pintype "passive"))
      (node (ref "SYNC") (pin "P$3") (pinfunction "1_P$3") (pintype "passive"))
      (node (ref "TRIG_OUT") (pin "P$3") (pinfunction "1_P$3") (pintype "passive"))
      (node (ref "U1") (pin "1") (pinfunction "~{OE}_1") (pintype "input"))
      (node (ref "U1") (pin "3") (pinfunction "GND_3") (pintype "power_in"))
      (node (ref "WAVE") (pin "P$2") (pinfunction "3_P$2") (pintype "passive"))
      (node (ref "WAVE") (pin "P$3") (pinfunction "1_P$3") (pintype "passive"))
    )
    (net (code "8") (name "Net-(-5V-3)") (class "Default")
      (node (ref "-5V") (pin "1") (pinfunction "3_1") (pintype "passive"))
      (node (ref "VR1") (pin "1") (pinfunction "A_1") (pintype "passive"))
      (node (ref "VR2") (pin "1") (pinfunction "A_1") (pintype "passive"))
      (node (ref "VR3") (pin "1") (pinfunction "A_1") (pintype "passive"))
      (node (ref "VR4") (pin "1") (pinfunction "A_1") (pintype "passive"))
    )
    (net (code "9") (name "Net-(5-3)") (class "Default")
      (node (ref "5") (pin "1") (pinfunction "3_1") (pintype "passive"))
      (node (ref "U1") (pin "2") (pinfunction "A_2") (pintype "input"))
    )
    (net (code "10") (name "Net-(AMP-2)") (class "Default")
      (node (ref "AMP") (pin "P$1") (pinfunction "2_P$1") (pintype "passive"))
      (node (ref "CV5") (pin "1") (pinfunction "3_1") (pintype "passive"))
    )
    (net (code "11") (name "Net-(CV1-3)") (class "Default")
      (node (ref "CV1") (pin "1") (pinfunction "3_1") (pintype "passive"))
      (node (ref "SYNC") (pin "P$1") (pinfunction "2_P$1") (pintype "passive"))
    )
    (net (code "12") (name "Net-(CV2-3)") (class "Default")
      (node (ref "CV2") (pin "1") (pinfunction "3_1") (pintype "passive"))
      (node (ref "WAVE") (pin "P$1") (pinfunction "2_P$1") (pintype "passive"))
    )
    (net (code "13") (name "Net-(CV2_-3)") (class "Default")
      (node (ref "CV2_") (pin "1") (pinfunction "3_1") (pintype "passive"))
      (node (ref "VR3") (pin "2") (pinfunction "S_2") (pintype "passive"))
    )
    (net (code "14") (name "Net-(CV3-3)") (class "Default")
      (node (ref "CV3") (pin "1") (pinfunction "3_1") (pintype "passive"))
      (node (ref "FREQ") (pin "P$1") (pinfunction "2_P$1") (pintype "passive"))
    )
    (net (code "15") (name "Net-(CV3_-3)") (class "Default")
      (node (ref "CV3_") (pin "1") (pinfunction "3_1") (pintype "passive"))
      (node (ref "VR2") (pin "2") (pinfunction "S_2") (pintype "passive"))
    )
    (net (code "16") (name "Net-(CV4-3)") (class "Default")
      (node (ref "CV4") (pin "1") (pinfunction "3_1") (pintype "passive"))
      (node (ref "PHASE") (pin "P$1") (pinfunction "2_P$1") (pintype "passive"))
    )
    (net (code "17") (name "Net-(CV4_-3)") (class "Default")
      (node (ref "CV4_") (pin "1") (pinfunction "3_1") (pintype "passive"))
      (node (ref "VR1") (pin "2") (pinfunction "S_2") (pintype "passive"))
    )
    (net (code "18") (name "Net-(CV5_-3)") (class "Default")
      (node (ref "CV5_") (pin "1") (pinfunction "3_1") (pintype "passive"))
      (node (ref "VR4") (pin "2") (pinfunction "S_2") (pintype "passive"))
    )
    (net (code "19") (name "Net-(CVO1-3)") (class "Default")
      (node (ref "CVO1") (pin "1") (pinfunction "3_1") (pintype "passive"))
      (node (ref "OU1") (pin "P$1") (pinfunction "2_P$1") (pintype "passive"))
    )
    (net (code "20") (name "Net-(CVO2-3)") (class "Default")
      (node (ref "CVO2") (pin "1") (pinfunction "3_1") (pintype "passive"))
      (node (ref "OUT2") (pin "P$1") (pinfunction "2_P$1") (pintype "passive"))
    )
    (net (code "21") (name "Net-(CVO3-3)") (class "Default")
      (node (ref "CVO3") (pin "1") (pinfunction "3_1") (pintype "passive"))
      (node (ref "OUT3") (pin "P$1") (pinfunction "2_P$1") (pintype "passive"))
    )
    (net (code "22") (name "Net-(CVO4-3)") (class "Default")
      (node (ref "CVO4") (pin "1") (pinfunction "3_1") (pintype "passive"))
      (node (ref "OUT4") (pin "P$1") (pinfunction "2_P$1") (pintype "passive"))
    )
    (net (code "23") (name "Net-(CVO5-3)") (class "Default")
      (node (ref "CVO5") (pin "1") (pinfunction "3_1") (pintype "passive"))
      (node (ref "OUT5") (pin "P$1") (pinfunction "2_P$1") (pintype "passive"))
    )
    (net (code "24") (name "Net-(CVO6-3)") (class "Default")
      (node (ref "CVO6") (pin "1") (pinfunction "3_1") (pintype "passive"))
      (node (ref "OUT6") (pin "P$1") (pinfunction "2_P$1") (pintype "passive"))
    )
    (net (code "25") (name "Net-(CVO7-3)") (class "Default")
      (node (ref "CVO7") (pin "1") (pinfunction "3_1") (pintype "passive"))
      (node (ref "OUT7") (pin "P$1") (pinfunction "2_P$1") (pintype "passive"))
    )
    (net (code "26") (name "Net-(CVO8-3)") (class "Default")
      (node (ref "CVO8") (pin "1") (pinfunction "3_1") (pintype "passive"))
      (node (ref "OUT8") (pin "P$1") (pinfunction "2_P$1") (pintype "passive"))
    )
    (net (code "27") (name "Net-(ENC1-3)") (class "Default")
      (node (ref "ENC1") (pin "1") (pinfunction "3_1") (pintype "passive"))
      (node (ref "SW1") (pin "B") (pinfunction "B_B") (pintype "passive"))
    )
    (net (code "28") (name "Net-(ENC2-3)") (class "Default")
      (node (ref "ENC2") (pin "1") (pinfunction "3_1") (pintype "passive"))
      (node (ref "SW1") (pin "A") (pinfunction "A_A") (pintype "passive"))
    )
    (net (code "29") (name "Net-(ENCBTN-3)") (class "Default")
      (node (ref "ENCBTN") (pin "1") (pinfunction "3_1") (pintype "passive"))
      (node (ref "SW1") (pin "P2") (pinfunction "2_P2") (pintype "passive"))
    )
    (net (code "30") (name "Net-(IC1-CS1)") (class "Default")
      (node (ref "IC1") (pin "20") (pinfunction "CS1_20") (pintype "output"))
      (node (ref "LED1") (pin "2") (pinfunction "A_2") (pintype "bidirectional"))
      (node (ref "LED16") (pin "A") (pinfunction "A_A") (pintype "passive"))
      (node (ref "LED9") (pin "A") (pinfunction "A_A") (pintype "passive"))
    )
    (net (code "31") (name "Net-(IC1-CS2)") (class "Default")
      (node (ref "IC1") (pin "21") (pinfunction "CS2_21") (pintype "output"))
      (node (ref "LED13") (pin "A") (pinfunction "A_A") (pintype "passive"))
      (node (ref "LED15") (pin "A") (pinfunction "A_A") (pintype "passive"))
      (node (ref "LED2") (pin "2") (pinfunction "A_2") (pintype "bidirectional"))
    )
    (net (code "32") (name "Net-(IC1-CS3)") (class "Default")
      (node (ref "IC1") (pin "23") (pinfunction "CS3_23") (pintype "bidirectional"))
      (node (ref "LED12") (pin "A") (pinfunction "A_A") (pintype "passive"))
      (node (ref "LED14") (pin "A") (pinfunction "A_A") (pintype "passive"))
      (node (ref "LED3") (pin "2") (pinfunction "A_2") (pintype "bidirectional"))
    )
    (net (code "33") (name "Net-(IC1-CS4)") (class "Default")
      (node (ref "IC1") (pin "24") (pinfunction "CS4_24") (pintype "bidirectional"))
      (node (ref "LED11") (pin "A") (pinfunction "A_A") (pintype "passive"))
      (node (ref "LED21") (pin "A") (pinfunction "A_A") (pintype "passive"))
      (node (ref "LED4") (pin "2") (pinfunction "A_2") (pintype "bidirectional"))
    )
    (net (code "34") (name "Net-(IC1-CS5)") (class "Default")
      (node (ref "IC1") (pin "25") (pinfunction "CS5_25") (pintype "bidirectional"))
      (node (ref "LED10") (pin "A") (pinfunction "A_A") (pintype "passive"))
      (node (ref "LED22") (pin "A") (pinfunction "A_A") (pintype "passive"))
      (node (ref "LED5") (pin "2") (pinfunction "A_2") (pintype "bidirectional"))
    )
    (net (code "35") (name "Net-(IC1-CS6)") (class "Default")
      (node (ref "IC1") (pin "26") (pinfunction "CS6_26") (pintype "bidirectional"))
      (node (ref "LED20") (pin "A") (pinfunction "A_A") (pintype "passive"))
      (node (ref "LED23") (pin "A") (pinfunction "A_A") (pintype "passive"))
      (node (ref "LED6") (pin "2") (pinfunction "A_2") (pintype "bidirectional"))
    )
    (net (code "36") (name "Net-(IC1-CS7)") (class "Default")
      (node (ref "IC1") (pin "28") (pinfunction "CS7_28") (pintype "output"))
      (node (ref "LED19") (pin "A") (pinfunction "A_A") (pintype "passive"))
      (node (ref "LED24") (pin "A") (pinfunction "A_A") (pintype "passive"))
      (node (ref "LED7") (pin "2") (pinfunction "A_2") (pintype "bidirectional"))
    )
    (net (code "37") (name "Net-(IC1-CS8)") (class "Default")
      (node (ref "IC1") (pin "1") (pinfunction "CS8_1") (pintype "output"))
      (node (ref "LED17") (pin "A") (pinfunction "A_A") (pintype "passive"))
      (node (ref "LED18") (pin "A") (pinfunction "A_A") (pintype "passive"))
      (node (ref "LED8") (pin "2") (pinfunction "A_2") (pintype "bidirectional"))
    )
    (net (code "38") (name "Net-(IC1-R_EXT)") (class "Default")
      (node (ref "IC1") (pin "2") (pinfunction "R_EXT_2") (pintype "input"))
      (node (ref "R17") (pin "2") (pinfunction "2_2") (pintype "passive"))
    )
    (net (code "39") (name "Net-(IC1-SDB)") (class "Default")
      (node (ref "IC1") (pin "10") (pinfunction "SDB_10") (pintype "input"))
      (node (ref "R18") (pin "2") (pinfunction "2_2") (pintype "passive"))
    )
    (net (code "40") (name "Net-(IC1-SW1)") (class "Default")
      (node (ref "IC1") (pin "12") (pinfunction "SW1_12") (pintype "output"))
      (node (ref "LED1") (pin "1") (pinfunction "RED_1") (pintype "bidirectional"))
      (node (ref "LED2") (pin "1") (pinfunction "RED_1") (pintype "bidirectional"))
      (node (ref "LED3") (pin "1") (pinfunction "RED_1") (pintype "bidirectional"))
      (node (ref "LED4") (pin "1") (pinfunction "RED_1") (pintype "bidirectional"))
      (node (ref "LED5") (pin "1") (pinfunction "RED_1") (pintype "bidirectional"))
      (node (ref "LED6") (pin "1") (pinfunction "RED_1") (pintype "bidirectional"))
      (node (ref "LED7") (pin "1") (pinfunction "RED_1") (pintype "bidirectional"))
      (node (ref "LED8") (pin "1") (pinfunction "RED_1") (pintype "bidirectional"))
    )
    (net (code "41") (name "Net-(IC1-SW2)") (class "Default")
      (node (ref "IC1") (pin "13") (pinfunction "SW2_13") (pintype "output"))
      (node (ref "LED1") (pin "3") (pinfunction "GRN_3") (pintype "bidirectional"))
      (node (ref "LED2") (pin "3") (pinfunction "GRN_3") (pintype "bidirectional"))
      (node (ref "LED3") (pin "3") (pinfunction "GRN_3") (pintype "bidirectional"))
      (node (ref "LED4") (pin "3") (pinfunction "GRN_3") (pintype "bidirectional"))
      (node (ref "LED5") (pin "3") (pinfunction "GRN_3") (pintype "bidirectional"))
      (node (ref "LED6") (pin "3") (pinfunction "GRN_3") (pintype "bidirectional"))
      (node (ref "LED7") (pin "3") (pinfunction "GRN_3") (pintype "bidirectional"))
      (node (ref "LED8") (pin "3") (pinfunction "GRN_3") (pintype "bidirectional"))
    )
    (net (code "42") (name "Net-(IC1-SW3)") (class "Default")
      (node (ref "IC1") (pin "15") (pinfunction "SW3_15") (pintype "output"))
      (node (ref "LED10") (pin "C") (pinfunction "C_C") (pintype "passive"))
      (node (ref "LED11") (pin "C") (pinfunction "C_C") (pintype "passive"))
      (node (ref "LED12") (pin "C") (pinfunction "C_C") (pintype "passive"))
      (node (ref "LED13") (pin "C") (pinfunction "C_C") (pintype "passive"))
      (node (ref "LED18") (pin "C") (pinfunction "C_C") (pintype "passive"))
      (node (ref "LED19") (pin "C") (pinfunction "C_C") (pintype "passive"))
      (node (ref "LED20") (pin "C") (pinfunction "C_C") (pintype "passive"))
      (node (ref "LED9") (pin "C") (pinfunction "C_C") (pintype "passive"))
    )
    (net (code "43") (name "Net-(IC1-SW4)") (class "Default")
      (node (ref "IC1") (pin "16") (pinfunction "SW4_16") (pintype "output"))
      (node (ref "LED14") (pin "C") (pinfunction "C_C") (pintype "passive"))
      (node (ref "LED15") (pin "C") (pinfunction "C_C") (pintype "passive"))
      (node (ref "LED16") (pin "C") (pinfunction "C_C") (pintype "passive"))
      (node (ref "LED17") (pin "C") (pinfunction "C_C") (pintype "passive"))
      (node (ref "LED21") (pin "C") (pinfunction "C_C") (pintype "passive"))
      (node (ref "LED22") (pin "C") (pinfunction "C_C") (pintype "passive"))
      (node (ref "LED23") (pin "C") (pinfunction "C_C") (pintype "passive"))
      (node (ref "LED24") (pin "C") (pinfunction "C_C") (pintype "passive"))
    )
    (net (code "44") (name "Net-(IC1-SW5)") (class "Default")
      (node (ref "IC1") (pin "17") (pinfunction "SW5_17") (pintype "output"))
      (node (ref "LED1") (pin "4") (pinfunction "BLU_4") (pintype "bidirectional"))
      (node (ref "LED2") (pin "4") (pinfunction "BLU_4") (pintype "bidirectional"))
      (node (ref "LED3") (pin "4") (pinfunction "BLU_4") (pintype "bidirectional"))
      (node (ref "LED4") (pin "4") (pinfunction "BLU_4") (pintype "bidirectional"))
      (node (ref "LED5") (pin "4") (pinfunction "BLU_4") (pintype "bidirectional"))
      (node (ref "LED6") (pin "4") (pinfunction "BLU_4") (pintype "bidirectional"))
      (node (ref "LED7") (pin "4") (pinfunction "BLU_4") (pintype "bidirectional"))
      (node (ref "LED8") (pin "4") (pinfunction "BLU_4") (pintype "bidirectional"))
    )
    (net (code "45") (name "Net-(TRIG_OUT-2)") (class "Default")
      (node (ref "R56") (pin "1") (pinfunction "1_1") (pintype "passive"))
      (node (ref "TRIG_OUT") (pin "P$1") (pinfunction "2_P$1") (pintype "passive"))
    )
    (net (code "46") (name "Net-(U1A-Y)") (class "Default")
      (node (ref "R56") (pin "2") (pinfunction "2_2") (pintype "passive"))
      (node (ref "U1") (pin "4") (pinfunction "Y_4") (pintype "tri_state"))
    )
    (net (code "47") (name "unconnected-(0_RX-3-Pad1)") (class "Default")
      (node (ref "0_RX") (pin "1") (pinfunction "3_1") (pintype "passive"))
    )
    (net (code "48") (name "unconnected-(1_TX-3-Pad1)") (class "Default")
      (node (ref "1_TX") (pin "1") (pinfunction "3_1") (pintype "passive"))
    )
    (net (code "49") (name "unconnected-(6-3-Pad1)") (class "Default")
      (node (ref "6") (pin "1") (pinfunction "3_1") (pintype "passive"))
    )
    (net (code "50") (name "unconnected-(7-3-Pad1)") (class "Default")
      (node (ref "7") (pin "1") (pinfunction "3_1") (pintype "passive"))
    )
    (net (code "51") (name "unconnected-(28-3-Pad1)") (class "Default")
      (node (ref "28") (pin "1") (pinfunction "3_1") (pintype "passive"))
    )
    (net (code "52") (name "unconnected-(29-3-Pad1)") (class "Default")
      (node (ref "29") (pin "1") (pinfunction "3_1") (pintype "passive"))
    )
    (net (code "53") (name "unconnected-(30-3-Pad1)") (class "Default")
      (node (ref "30") (pin "1") (pinfunction "3_1") (pintype "passive"))
    )
    (net (code "54") (name "unconnected-(31-3-Pad1)") (class "Default")
      (node (ref "31") (pin "1") (pinfunction "3_1") (pintype "passive"))
    )
    (net (code "55") (name "unconnected-(32-3-Pad1)") (class "Default")
      (node (ref "32") (pin "1") (pinfunction "3_1") (pintype "passive"))
    )
    (net (code "56") (name "unconnected-(33-3-Pad1)") (class "Default")
      (node (ref "33") (pin "1") (pinfunction "3_1") (pintype "passive"))
    )
    (net (code "57") (name "unconnected-(34-3-Pad1)") (class "Default")
      (node (ref "34") (pin "1") (pinfunction "3_1") (pintype "passive"))
    )
    (net (code "58") (name "unconnected-(35-3-Pad1)") (class "Default")
      (node (ref "35") (pin "1") (pinfunction "3_1") (pintype "passive"))
    )
    (net (code "59") (name "unconnected-(36-3-Pad1)") (class "Default")
      (node (ref "36") (pin "1") (pinfunction "3_1") (pintype "passive"))
    )
    (net (code "60") (name "unconnected-(37-3-Pad1)") (class "Default")
      (node (ref "37") (pin "1") (pinfunction "3_1") (pintype "passive"))
    )
    (net (code "61") (name "unconnected-(38-3-Pad1)") (class "Default")
      (node (ref "38") (pin "1") (pinfunction "3_1") (pintype "passive"))
    )
    (net (code "62") (name "unconnected-(39-3-Pad1)") (class "Default")
      (node (ref "39") (pin "1") (pinfunction "3_1") (pintype "passive"))
    )
    (net (code "63") (name "unconnected-(40-3-Pad1)") (class "Default")
      (node (ref "40") (pin "1") (pinfunction "3_1") (pintype "passive"))
    )
    (net (code "64") (name "unconnected-(41-3-Pad1)") (class "Default")
      (node (ref "41") (pin "1") (pinfunction "3_1") (pintype "passive"))
    )
    (net (code "65") (name "unconnected-(CV1_-3-Pad1)") (class "Default")
      (node (ref "CV1_") (pin "1") (pinfunction "3_1") (pintype "passive"))
    )
    (net (code "66") (name "unconnected-(CV6-3-Pad1)") (class "Default")
      (node (ref "CV6") (pin "1") (pinfunction "3_1") (pintype "passive"))
    )
    (net (code "67") (name "unconnected-(CV6_-3-Pad1)") (class "Default")
      (node (ref "CV6_") (pin "1") (pinfunction "3_1") (pintype "passive"))
    )
    (net (code "68") (name "unconnected-(CV7-3-Pad1)") (class "Default")
      (node (ref "CV7") (pin "1") (pinfunction "3_1") (pintype "passive"))
    )
    (net (code "69") (name "unconnected-(CV7_-3-Pad1)") (class "Default")
      (node (ref "CV7_") (pin "1") (pinfunction "3_1") (pintype "passive"))
    )
    (net (code "70") (name "unconnected-(CV8-3-Pad1)") (class "Default")
      (node (ref "CV8") (pin "1") (pinfunction "3_1") (pintype "passive"))
    )
    (net (code "71") (name "unconnected-(CV8_-3-Pad1)") (class "Default")
      (node (ref "CV8_") (pin "1") (pinfunction "3_1") (pintype "passive"))
    )
    (net (code "72") (name "unconnected-(CV9-3-Pad1)") (class "Default")
      (node (ref "CV9") (pin "1") (pinfunction "3_1") (pintype "passive"))
    )
    (net (code "73") (name "unconnected-(CV9_-3-Pad1)") (class "Default")
      (node (ref "CV9_") (pin "1") (pinfunction "3_1") (pintype "passive"))
    )
    (net (code "74") (name "unconnected-(CV10-3-Pad1)") (class "Default")
      (node (ref "CV10") (pin "1") (pinfunction "3_1") (pintype "passive"))
    )
    (net (code "75") (name "unconnected-(CV10_-3-Pad1)") (class "Default")
      (node (ref "CV10_") (pin "1") (pinfunction "3_1") (pintype "passive"))
    )
    (net (code "76") (name "unconnected-(CV11-3-Pad1)") (class "Default")
      (node (ref "CV11") (pin "1") (pinfunction "3_1") (pintype "passive"))
    )
    (net (code "77") (name "unconnected-(CV11_-3-Pad1)") (class "Default")
      (node (ref "CV11_") (pin "1") (pinfunction "3_1") (pintype "passive"))
    )
    (net (code "78") (name "unconnected-(CV12-3-Pad1)") (class "Default")
      (node (ref "CV12") (pin "1") (pinfunction "3_1") (pintype "passive"))
    )
    (net (code "79") (name "unconnected-(CV12_-3-Pad1)") (class "Default")
      (node (ref "CV12_") (pin "1") (pinfunction "3_1") (pintype "passive"))
    )
    (net (code "80") (name "unconnected-(IC1-INTB-Pad9)") (class "Default")
      (node (ref "IC1") (pin "9") (pinfunction "INTB_9") (pintype "input"))
    )
    (net (code "81") (name "unconnected-(IC1-SW6-Pad19)") (class "Default")
      (node (ref "IC1") (pin "19") (pinfunction "SW6_19") (pintype "output"))
    )
    (net (code "82") (name "unconnected-(IC1-SYNC-Pad5)") (class "Default")
      (node (ref "IC1") (pin "5") (pinfunction "SYNC_5") (pintype "input"))
    )
    (net (code "83") (name "unconnected-(IO1-3-Pad1)") (class "Default")
      (node (ref "IO1") (pin "1") (pinfunction "3_1") (pintype "passive"))
    )
    (net (code "84") (name "unconnected-(IO2-3-Pad1)") (class "Default")
      (node (ref "IO2") (pin "1") (pinfunction "3_1") (pintype "passive"))
    )
    (net (code "85") (name "unconnected-(IO3-3-Pad1)") (class "Default")
      (node (ref "IO3") (pin "1") (pinfunction "3_1") (pintype "passive"))
    )
    (net (code "86") (name "unconnected-(IO4-3-Pad1)") (class "Default")
      (node (ref "IO4") (pin "1") (pinfunction "3_1") (pintype "passive"))
    )
    (net (code "87") (name "unconnected-(IO5-3-Pad1)") (class "Default")
      (node (ref "IO5") (pin "1") (pinfunction "3_1") (pintype "passive"))
    )
    (net (code "88") (name "unconnected-(IO6-3-Pad1)") (class "Default")
      (node (ref "IO6") (pin "1") (pinfunction "3_1") (pintype "passive"))
    )
    (net (code "89") (name "unconnected-(IO7-3-Pad1)") (class "Default")
      (node (ref "IO7") (pin "1") (pinfunction "3_1") (pintype "passive"))
    )
    (net (code "90") (name "unconnected-(IO8-3-Pad1)") (class "Default")
      (node (ref "IO8") (pin "1") (pinfunction "3_1") (pintype "passive"))
    )
    (net (code "91") (name "unconnected-(IO9-3-Pad1)") (class "Default")
      (node (ref "IO9") (pin "1") (pinfunction "3_1") (pintype "passive"))
    )
    (net (code "92") (name "unconnected-(IO10-3-Pad1)") (class "Default")
      (node (ref "IO10") (pin "1") (pinfunction "3_1") (pintype "passive"))
    )
    (net (code "93") (name "unconnected-(IO11-3-Pad1)") (class "Default")
      (node (ref "IO11") (pin "1") (pinfunction "3_1") (pintype "passive"))
    )
    (net (code "94") (name "unconnected-(IO12-3-Pad1)") (class "Default")
      (node (ref "IO12") (pin "1") (pinfunction "3_1") (pintype "passive"))
    )
    (net (code "95") (name "unconnected-(IO13-3-Pad1)") (class "Default")
      (node (ref "IO13") (pin "1") (pinfunction "3_1") (pintype "passive"))
    )
    (net (code "96") (name "unconnected-(IO14-3-Pad1)") (class "Default")
      (node (ref "IO14") (pin "1") (pinfunction "3_1") (pintype "passive"))
    )
    (net (code "97") (name "unconnected-(IO15-3-Pad1)") (class "Default")
      (node (ref "IO15") (pin "1") (pinfunction "3_1") (pintype "passive"))
    )
    (net (code "98") (name "unconnected-(IO16-3-Pad1)") (class "Default")
      (node (ref "IO16") (pin "1") (pinfunction "3_1") (pintype "passive"))
    )
    (net (code "99") (name "unconnected-(OU1-3-PadP$2)") (class "Default")
      (node (ref "OU1") (pin "P$2") (pinfunction "3_P$2") (pintype "passive"))
    )
    (net (code "100") (name "unconnected-(OUT2-3-PadP$2)") (class "Default")
      (node (ref "OUT2") (pin "P$2") (pinfunction "3_P$2") (pintype "passive"))
    )
    (net (code "101") (name "unconnected-(OUT3-3-PadP$2)") (class "Default")
      (node (ref "OUT3") (pin "P$2") (pinfunction "3_P$2") (pintype "passive"))
    )
    (net (code "102") (name "unconnected-(OUT4-3-PadP$2)") (class "Default")
      (node (ref "OUT4") (pin "P$2") (pinfunction "3_P$2") (pintype "passive"))
    )
    (net (code "103") (name "unconnected-(OUT5-3-PadP$2)") (class "Default")
      (node (ref "OUT5") (pin "P$2") (pinfunction "3_P$2") (pintype "passive"))
    )
    (net (code "104") (name "unconnected-(OUT6-3-PadP$2)") (class "Default")
      (node (ref "OUT6") (pin "P$2") (pinfunction "3_P$2") (pintype "passive"))
    )
    (net (code "105") (name "unconnected-(OUT7-3-PadP$2)") (class "Default")
      (node (ref "OUT7") (pin "P$2") (pinfunction "3_P$2") (pintype "passive"))
    )
    (net (code "106") (name "unconnected-(OUT8-3-PadP$2)") (class "Default")
      (node (ref "OUT8") (pin "P$2") (pinfunction "3_P$2") (pintype "passive"))
    )
    (net (code "107") (name "unconnected-(TRIG_OUT-3-PadP$2)") (class "Default")
      (node (ref "TRIG_OUT") (pin "P$2") (pinfunction "3_P$2") (pintype "passive"))
    )
  )
)
